# 1-Schematic_IRWAVER_MODULE.net
KiCad netlist of a schematic drawn in EasyEDA
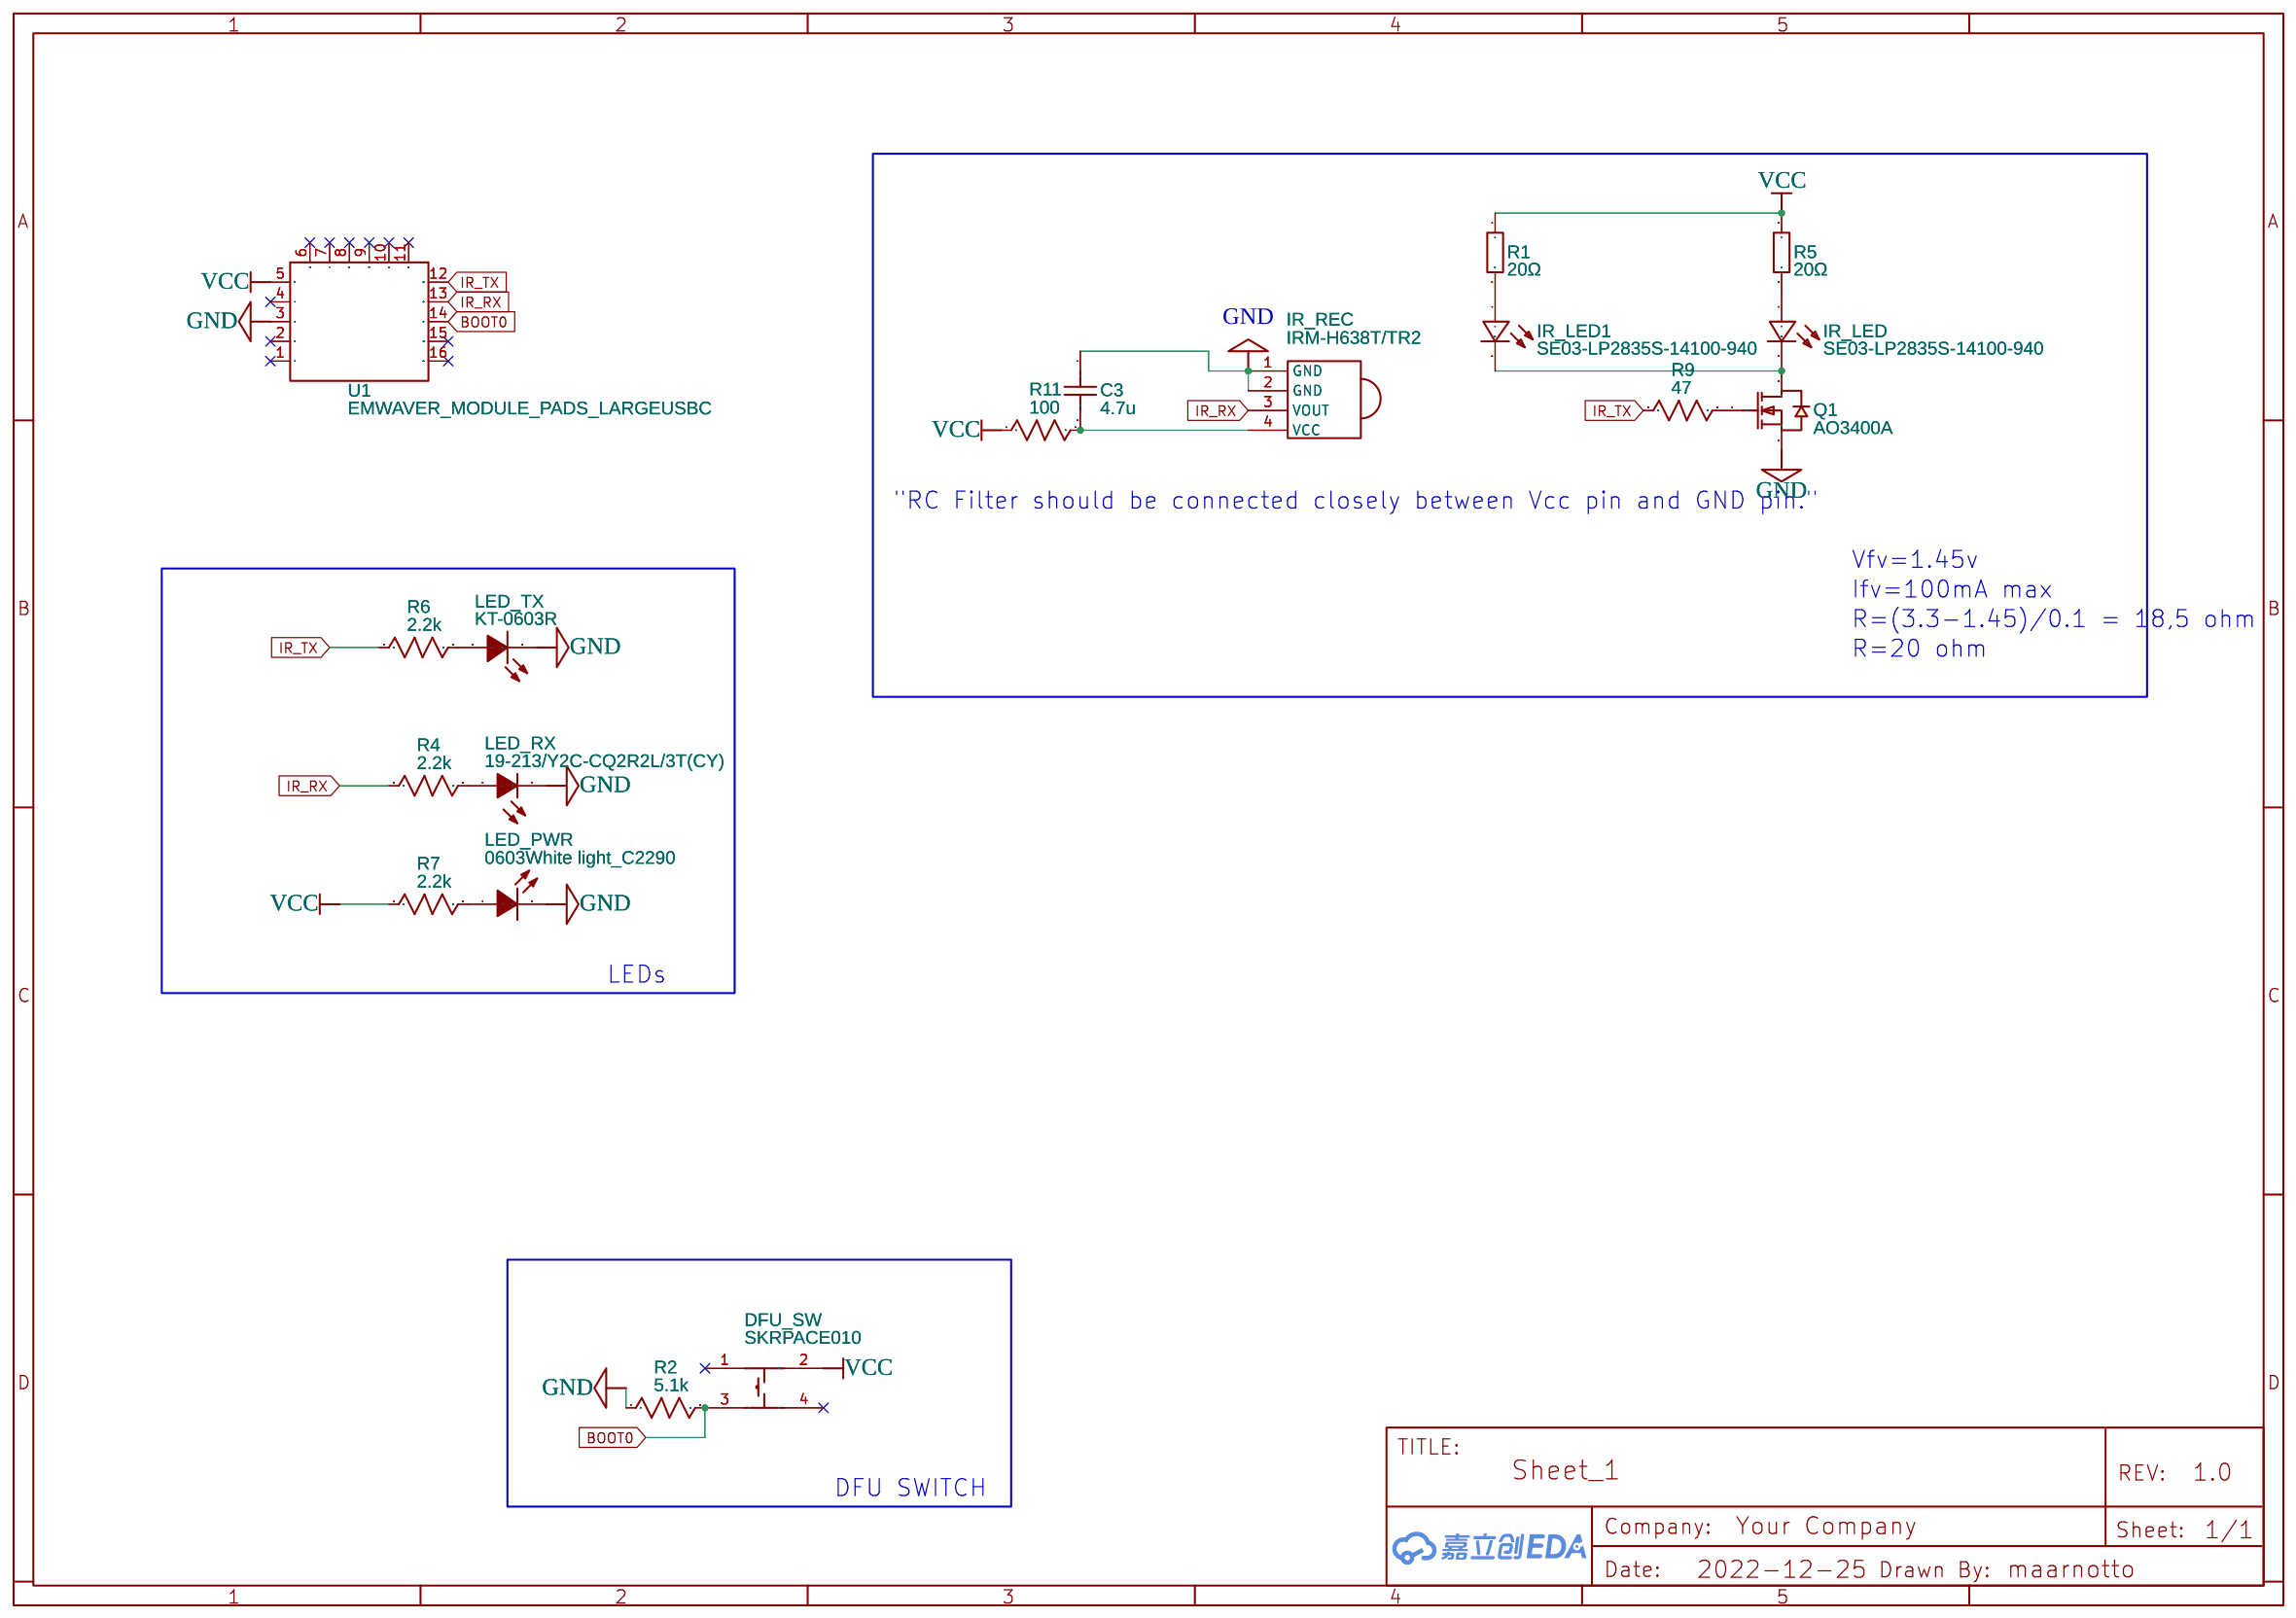
[diagram p0: schematic sheet]

(export (version "E")
  (design (tool "Eeschema 10.0.6"))
  (components
    (comp (ref "C3") (value "4.7u") (libsource (lib "") (part "C_0603_US")))
    (comp (ref "DFU_SW")
      (value "SKRPACE010")
      (fields (field (name "Manufacturer") "ALPSALPINE(阿尔卑斯阿尔派)"))
      (libsource (lib "") (part "SKRPACE010"))
    )
    (comp (ref "IR_LED")
      (value "SE03-LP2835S-14100-940")
      (fields (field (name "Manufacturer") "XSSY(旭晟)"))
      (libsource (lib "") (part "SE03-LP2835S-14100-940"))
    )
    (comp (ref "IR_LED1")
      (value "SE03-LP2835S-14100-940")
      (fields (field (name "Manufacturer") "XSSY(旭晟)"))
      (libsource (lib "") (part "SE03-LP2835S-14100-940"))
    )
    (comp (ref "IR_REC")
      (value "IRM-H638T/TR2")
      (fields (field (name "Manufacturer") "EVERLIGHT(亿光)"))
      (libsource (lib "") (part "IRM-H638T/TR2"))
    )
    (comp (ref "LED_PWR")
      (value "0603White light_C2290")
      (fields (field (name "Manufacturer Part") "KT-0603白灯"))
      (libsource (lib "") (part "0603White light_C2290"))
    )
    (comp (ref "LED_RX")
      (value "19-213/Y2C-CQ2R2L/3T(CY)")
      (fields (field (name "Manufacturer") "EVERLIGHT(亿光)"))
      (libsource (lib "") (part "19-213/Y2C-CQ2R2L/3T(CY)"))
    )
    (comp (ref "LED_TX")
      (value "KT-0603R")
      (fields (field (name "Manufacturer") "KENTO"))
      (libsource (lib "") (part "KT-0603R"))
    )
    (comp (ref "Q1")
      (value "AO3400A")
      (fields (field (name "Manufacturer") "AOS"))
      (libsource (lib "") (part "AO3400A"))
    )
    (comp (ref "R1")
      (value "20Ω")
      (fields
        (field (name "Manufacturer Part") "1206W4F200JT5E")
        (field (name "Manufacturer") "UNI-ROYAL(厚声)")
      )
      (libsource (lib "") (part "1206W4F200JT5E"))
    )
    (comp (ref "R2") (value "5.1k") (libsource (lib "") (part "R_0603_US")))
    (comp (ref "R4") (value "2.2k") (libsource (lib "") (part "R_0603_US")))
    (comp (ref "R5")
      (value "20Ω")
      (fields
        (field (name "Manufacturer Part") "1206W4F200JT5E")
        (field (name "Manufacturer") "UNI-ROYAL(厚声)")
      )
      (libsource (lib "") (part "1206W4F200JT5E"))
    )
    (comp (ref "R6") (value "2.2k") (libsource (lib "") (part "R_0603_US")))
    (comp (ref "R7") (value "2.2k") (libsource (lib "") (part "R_0603_US")))
    (comp (ref "R9") (value "47") (libsource (lib "") (part "R_0603_US")))
    (comp (ref "R11") (value "100") (libsource (lib "") (part "R_0603_US")))
    (comp (ref "U1")
      (value "EMWAVER_MODULE_PADS_LARGEUSBC")
      (libsource (lib "") (part "EMWAVER_MODULE_PADS_LARGEUSBC"))
    )
  )
  (nets
    (net (code "1") (name "BOOT0") (class "Default")
      (node (ref "DFU_SW") (pin "3") (pinfunction "3_3") (pintype "unspecified"))
      (node (ref "R2") (pin "2") (pinfunction "2_2") (pintype "unspecified"))
      (node (ref "U1") (pin "14") (pinfunction "14_14") (pintype "unspecified"))
    )
    (net (code "2") (name "GND") (class "Default")
      (node (ref "C3") (pin "1") (pinfunction "1_1") (pintype "unspecified"))
      (node (ref "IR_REC") (pin "1") (pinfunction "GND_1") (pintype "input"))
      (node (ref "IR_REC") (pin "2") (pinfunction "GND_2") (pintype "input"))
      (node (ref "LED_PWR") (pin "2") (pinfunction "K_2") (pintype "unspecified"))
      (node (ref "LED_RX") (pin "1") (pinfunction "C_1") (pintype "input"))
      (node (ref "LED_TX") (pin "1") (pinfunction "K_1") (pintype "unspecified"))
      (node (ref "Q1") (pin "2") (pinfunction "S_2") (pintype "unspecified"))
      (node (ref "R2") (pin "1") (pinfunction "1_1") (pintype "unspecified"))
      (node (ref "U1") (pin "3") (pinfunction "3_3") (pintype "unspecified"))
    )
    (net (code "3") (name "IR_RX") (class "Default")
      (node (ref "IR_REC") (pin "3") (pinfunction "VOUT_3") (pintype "input"))
      (node (ref "R4") (pin "1") (pinfunction "1_1") (pintype "unspecified"))
      (node (ref "U1") (pin "13") (pinfunction "13_13") (pintype "unspecified"))
    )
    (net (code "4") (name "IR_TX") (class "Default")
      (node (ref "R6") (pin "1") (pinfunction "1_1") (pintype "unspecified"))
      (node (ref "R9") (pin "1") (pinfunction "1_1") (pintype "unspecified"))
      (node (ref "U1") (pin "12") (pinfunction "12_12") (pintype "unspecified"))
    )
    (net (code "5") (name "Net-(IR_LED-A)") (class "Default")
      (node (ref "IR_LED") (pin "1") (pinfunction "A_1") (pintype "unspecified"))
      (node (ref "R5") (pin "2") (pinfunction "2_2") (pintype "input"))
    )
    (net (code "6") (name "Net-(IR_LED-C)") (class "Default")
      (node (ref "IR_LED") (pin "2") (pinfunction "C_2") (pintype "unspecified"))
      (node (ref "IR_LED1") (pin "2") (pinfunction "C_2") (pintype "unspecified"))
      (node (ref "Q1") (pin "3") (pinfunction "D_3") (pintype "unspecified"))
    )
    (net (code "7") (name "Net-(IR_LED1-A)") (class "Default")
      (node (ref "IR_LED1") (pin "1") (pinfunction "A_1") (pintype "unspecified"))
      (node (ref "R1") (pin "2") (pinfunction "2_2") (pintype "input"))
    )
    (net (code "8") (name "Net-(IR_REC-VCC)") (class "Default")
      (node (ref "C3") (pin "2") (pinfunction "2_2") (pintype "unspecified"))
      (node (ref "IR_REC") (pin "4") (pinfunction "VCC_4") (pintype "input"))
      (node (ref "R11") (pin "2") (pinfunction "2_2") (pintype "unspecified"))
    )
    (net (code "9") (name "Net-(LED_PWR-A)") (class "Default")
      (node (ref "LED_PWR") (pin "1") (pinfunction "A_1") (pintype "unspecified"))
      (node (ref "R7") (pin "2") (pinfunction "2_2") (pintype "unspecified"))
    )
    (net (code "10") (name "Net-(LED_RX-A)") (class "Default")
      (node (ref "LED_RX") (pin "2") (pinfunction "A_2") (pintype "input"))
      (node (ref "R4") (pin "2") (pinfunction "2_2") (pintype "unspecified"))
    )
    (net (code "11") (name "Net-(LED_TX-A)") (class "Default")
      (node (ref "LED_TX") (pin "2") (pinfunction "A_2") (pintype "unspecified"))
      (node (ref "R6") (pin "2") (pinfunction "2_2") (pintype "unspecified"))
    )
    (net (code "12") (name "Net-(Q1-G)") (class "Default")
      (node (ref "Q1") (pin "1") (pinfunction "G_1") (pintype "unspecified"))
      (node (ref "R9") (pin "2") (pinfunction "2_2") (pintype "unspecified"))
    )
    (net (code "13") (name "VCC") (class "Default")
      (node (ref "DFU_SW") (pin "2") (pinfunction "2_2") (pintype "unspecified"))
      (node (ref "R1") (pin "1") (pinfunction "1_1") (pintype "input"))
      (node (ref "R11") (pin "1") (pinfunction "1_1") (pintype "unspecified"))
      (node (ref "R5") (pin "1") (pinfunction "1_1") (pintype "input"))
      (node (ref "R7") (pin "1") (pinfunction "1_1") (pintype "unspecified"))
      (node (ref "U1") (pin "5") (pinfunction "5_5") (pintype "unspecified"))
    )
    (net (code "14") (name "unconnected-(DFU_SW-Pad1)") (class "Default")
      (node (ref "DFU_SW") (pin "1") (pinfunction "1_1") (pintype "unspecified+no_connect"))
    )
    (net (code "15") (name "unconnected-(DFU_SW-Pad4)") (class "Default")
      (node (ref "DFU_SW") (pin "4") (pinfunction "4_4") (pintype "unspecified+no_connect"))
    )
    (net (code "16") (name "unconnected-(U1-Pad1)") (class "Default")
      (node (ref "U1") (pin "1") (pinfunction "1_1") (pintype "unspecified+no_connect"))
    )
    (net (code "17") (name "unconnected-(U1-Pad2)") (class "Default")
      (node (ref "U1") (pin "2") (pinfunction "2_2") (pintype "unspecified+no_connect"))
    )
    (net (code "18") (name "unconnected-(U1-Pad4)") (class "Default")
      (node (ref "U1") (pin "4") (pinfunction "4_4") (pintype "unspecified+no_connect"))
    )
    (net (code "19") (name "unconnected-(U1-Pad6)") (class "Default")
      (node (ref "U1") (pin "6") (pinfunction "6_6") (pintype "unspecified+no_connect"))
    )
    (net (code "20") (name "unconnected-(U1-Pad7)") (class "Default")
      (node (ref "U1") (pin "7") (pinfunction "7_7") (pintype "unspecified+no_connect"))
    )
    (net (code "21") (name "unconnected-(U1-Pad8)") (class "Default")
      (node (ref "U1") (pin "8") (pinfunction "8_8") (pintype "unspecified+no_connect"))
    )
    (net (code "22") (name "unconnected-(U1-Pad9)") (class "Default")
      (node (ref "U1") (pin "9") (pinfunction "9_9") (pintype "unspecified+no_connect"))
    )
    (net (code "23") (name "unconnected-(U1-Pad10)") (class "Default")
      (node (ref "U1") (pin "10") (pinfunction "10_10") (pintype "unspecified+no_connect"))
    )
    (net (code "24") (name "unconnected-(U1-Pad11)") (class "Default")
      (node (ref "U1") (pin "11") (pinfunction "11_11") (pintype "unspecified+no_connect"))
    )
    (net (code "25") (name "unconnected-(U1-Pad15)") (class "Default")
      (node (ref "U1") (pin "15") (pinfunction "15_15") (pintype "unspecified+no_connect"))
    )
    (net (code "26") (name "unconnected-(U1-Pad16)") (class "Default")
      (node (ref "U1") (pin "16") (pinfunction "16_16") (pintype "unspecified+no_connect"))
    )
  )
)
